# Fast_Servo.net
KiCad netlist of a schematic drawn in Altium Designer
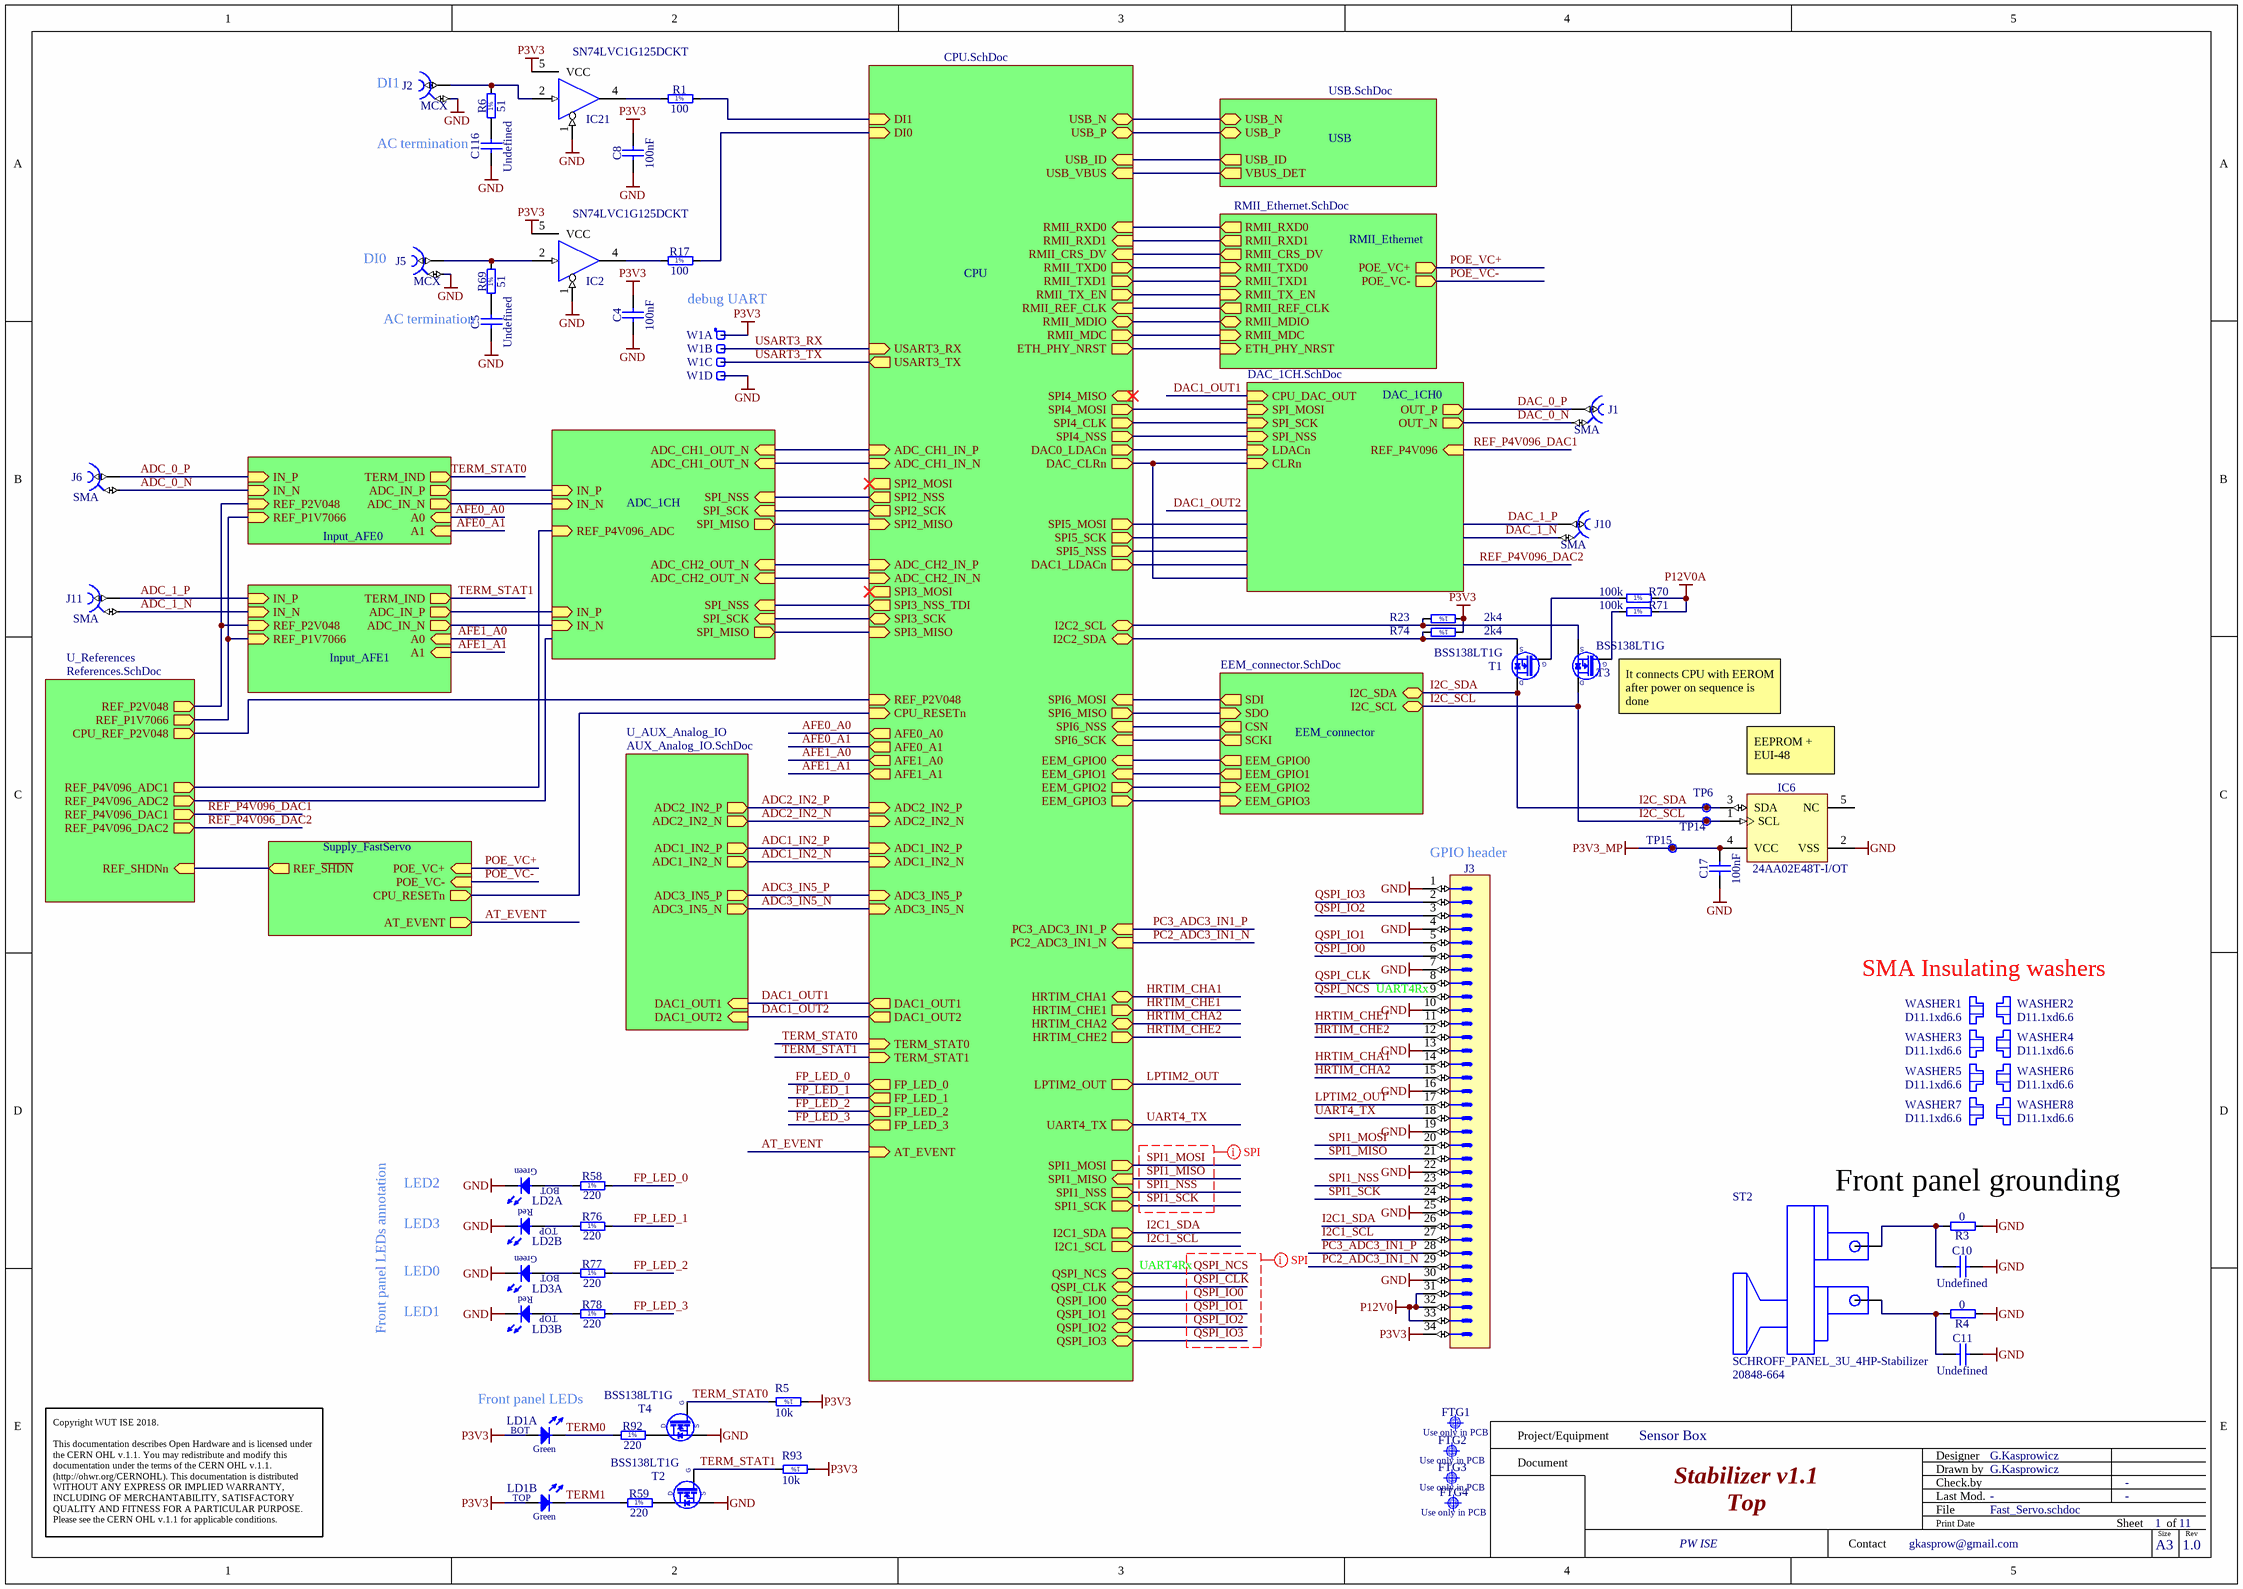
[diagram p0: Fast_Servo.schdoc]

(export (version "E")
  (design (tool "Eeschema 10.0.6"))
  (components
    (comp (ref "C4")
      (value "100nF")
      (footprint "CAPC1005X55N")
      (description "Non-polarised capacitor")
      (fields
        (field (name "PART NUMBER") "CC0402_100NF_16V_10%_X7R")
        (field (name "VOLTAGE") "16V")
        (field (name "AUTHOR") "CERN DEM JLC")
      )
      (libsource (lib "Capacitors") (part "Capacitor - non polarized"))
    )
    (comp (ref "C5")
      (value "Undefined")
      (footprint "CAPC1608X90N")
      (description "Non-polarised capacitor")
      (fields (field (name "PART NUMBER") "CC0603_NO-VALUE") (field (name "AUTHOR") "CERN DEM MR"))
      (libsource (lib "Capacitors") (part "Capacitor - non polarized"))
    )
    (comp (ref "C8")
      (value "100nF")
      (footprint "CAPC1005X55N")
      (description "Non-polarised capacitor")
      (fields
        (field (name "PART NUMBER") "CC0402_100NF_16V_10%_X7R")
        (field (name "VOLTAGE") "16V")
        (field (name "AUTHOR") "CERN DEM JLC")
      )
      (libsource (lib "Capacitors") (part "Capacitor - non polarized"))
    )
    (comp (ref "C10")
      (value "Undefined")
      (footprint "CAPC2012X135N")
      (description "Non-polarised capacitor")
      (fields (field (name "PART NUMBER") "CC0805_NO-VALUE") (field (name "AUTHOR") "CERN DEM JLC"))
      (libsource (lib "Capacitors") (part "Capacitor - non polarized"))
    )
    (comp (ref "C11")
      (value "Undefined")
      (footprint "CAPC2012X135N")
      (description "Non-polarised capacitor")
      (fields (field (name "PART NUMBER") "CC0805_NO-VALUE") (field (name "AUTHOR") "CERN DEM JLC"))
      (libsource (lib "Capacitors") (part "Capacitor - non polarized"))
    )
    (comp (ref "C17")
      (value "100nF")
      (footprint "CAPC1005X55N")
      (description "Non-polarised capacitor")
      (fields
        (field (name "PART NUMBER") "CC0402_100NF_16V_10%_X5R")
        (field (name "VOLTAGE") "16V")
        (field (name "AUTHOR") "CERN DEM JLC")
      )
      (libsource (lib "Capacitors") (part "Capacitor - non polarized"))
    )
    (comp (ref "C116")
      (value "Undefined")
      (footprint "CAPC1608X90N")
      (description "Non-polarised capacitor")
      (fields (field (name "PART NUMBER") "CC0603_NO-VALUE") (field (name "AUTHOR") "CERN DEM MR"))
      (libsource (lib "Capacitors") (part "Capacitor - non polarized"))
    )
    (comp (ref "FTG1")
      (value "Use only in PCB")
      (footprint "FIDUCIAL_TOP_C100-200")
      (description "Fiducial Target")
      (fields (field (name "PART NUMBER") "FIDUCIAL_TARGET_C100-200") (field (name "AUTHOR") "CERN DEM JLC"))
      (libsource (lib "Eletro-mechanical") (part "Fiducial Target"))
    )
    (comp (ref "FTG2")
      (value "Use only in PCB")
      (footprint "FIDUCIAL_TOP_S100-200")
      (description "Fiducial Target")
      (fields (field (name "PART NUMBER") "FIDUCIAL_TARGET_S100-200") (field (name "AUTHOR") "CERN DEM JLC"))
      (libsource (lib "Eletro-mechanical") (part "Fiducial Target"))
    )
    (comp (ref "FTG3")
      (value "Use only in PCB")
      (footprint "FIDUCIAL_TOP_S100-200")
      (description "Fiducial Target")
      (fields (field (name "PART NUMBER") "FIDUCIAL_TARGET_S100-200") (field (name "AUTHOR") "CERN DEM JLC"))
      (libsource (lib "Eletro-mechanical") (part "Fiducial Target"))
    )
    (comp (ref "FTG4")
      (value "Use only in PCB")
      (footprint "FIDUCIAL_TOP_S100-200")
      (description "Fiducial Target")
      (fields (field (name "PART NUMBER") "FIDUCIAL_TARGET_S100-200") (field (name "AUTHOR") "CERN DEM JLC"))
      (libsource (lib "Eletro-mechanical") (part "Fiducial Target"))
    )
    (comp (ref "IC2")
      (value "SN74LVC1G125DCKT")
      (footprint "SOT65P210X110-5N")
      (description "Single Bus Buffer Gate With 3-State Output")
      (fields (field (name "MANUFACTURER") "TEXAS INSTRUMENTS") (field (name "AUTHOR") "CERN DEM JLC"))
      (libsource (lib "ICs And Semiconductors") (part "741G125"))
    )
    (comp (ref "IC6")
      (value "24AA02E48T-I/OT")
      (footprint "SOT95P280X145-5N")
      (description "1.7V-5.5V, 2K I2C Serial EEPROM With EUI-48 Node Identity")
      (fields (field (name "MANUFACTURER") "MICROCHIP TECHNOLOGY") (field (name "AUTHOR") "CERN DEM MR"))
      (libsource (lib "ICs And Semiconductors") (part "24AA02E48T-I/OT"))
    )
    (comp (ref "IC21")
      (value "SN74LVC1G125DCKT")
      (footprint "SOT65P210X110-5N")
      (description "Single Bus Buffer Gate With 3-State Output")
      (fields (field (name "MANUFACTURER") "TEXAS INSTRUMENTS") (field (name "AUTHOR") "CERN DEM JLC"))
      (libsource (lib "ICs And Semiconductors") (part "741G125"))
    )
    (comp (ref "J1")
      (value "SMA")
      (footprint "RF249BT0050GHDW")
      (description "50 Ohm Through Hole SMA Right Angle PCB Jack")
      (fields
        (field (name "PART NUMBER") "AdamTech_RF249BT0050GHDW")
        (field (name "MANUFACTURER") "AdamTech")
        (field (name "AUTHOR") "GK")
      )
      (libsource (lib "LIBRARY_SCH") (part "CON_SMA_RF249BT0050GHDW"))
    )
    (comp (ref "J2")
      (value "MCX")
      (footprint "AMPHENOL_919-383J-51A")
      (fields
        (field (name "PART NUMBER") "AMPHENOL_919-383J-51A")
        (field (name "MANUFACTURER") "AMPHENOL")
        (field (name "MANUFACTURER PART NUMBER") "919-383J-51A")
        (field (name "AUTHOR") "CERN DEM BC")
      )
      (libsource (lib "Connectors") (part "Coax_1Female_1Shield"))
    )
    (comp (ref "J3")
      (value "Header 34")
      (footprint "3M_N2534-6002RB")
      (description "Connector 34 Male")
      (fields
        (field (name "PART NUMBER") "3M_N2534-6002RB")
        (field (name "MANUFACTURER") "3M")
        (field (name "AUTHOR") "CERN DEM JLC")
      )
      (libsource (lib "Connectors") (part "Connector 34 Male"))
    )
    (comp (ref "J5")
      (value "MCX")
      (footprint "AMPHENOL_919-383J-51A")
      (fields
        (field (name "PART NUMBER") "AMPHENOL_919-383J-51A")
        (field (name "MANUFACTURER") "AMPHENOL")
        (field (name "MANUFACTURER PART NUMBER") "919-383J-51A")
        (field (name "AUTHOR") "CERN DEM BC")
      )
      (libsource (lib "Connectors") (part "Coax_1Female_1Shield"))
    )
    (comp (ref "J6")
      (value "SMA")
      (footprint "RF249BT0050GHDW")
      (description "50 Ohm Through Hole SMA Right Angle PCB Jack")
      (fields
        (field (name "PART NUMBER") "AdamTech_RF249BT0050GHDW")
        (field (name "MANUFACTURER") "AdamTech")
        (field (name "AUTHOR") "GK")
      )
      (libsource (lib "") (part "CON_SMA_RF249BT0050GHDW_1"))
    )
    (comp (ref "J10")
      (value "SMA")
      (footprint "RF249BT0050GHDW")
      (description "50 Ohm Through Hole SMA Right Angle PCB Jack")
      (fields
        (field (name "PART NUMBER") "AdamTech_RF249BT0050GHDW")
        (field (name "MANUFACTURER") "AdamTech")
        (field (name "AUTHOR") "GK")
      )
      (libsource (lib "LIBRARY_SCH") (part "CON_SMA_RF249BT0050GHDW"))
    )
    (comp (ref "J11")
      (value "SMA")
      (footprint "RF249BT0050GHDW")
      (description "50 Ohm Through Hole SMA Right Angle PCB Jack")
      (fields
        (field (name "PART NUMBER") "AdamTech_RF249BT0050GHDW")
        (field (name "MANUFACTURER") "AdamTech")
        (field (name "AUTHOR") "GK")
      )
      (libsource (lib "") (part "CON_SMA_RF249BT0050GHDW_1"))
    )
    (comp (ref "LD1")
      (value "Green/Green")
      (footprint "LED_DIALIGHT_571-0122F")
      (description "LED x2 Green 1C2A-BOT_3C4A-TOP")
      (fields
        (field (name "PART NUMBER") "LED_DIALIGHT_571-0122F")
        (field (name "MANUFACTURER") "DIALIGHT")
        (field (name "AUTHOR") "CERN DEM JLC")
      )
      (libsource (lib "ICs And Semiconductors") (part "LED x2 Green 1C2A-BOT_3C4A-TOP"))
    )
    (comp (ref "LD2")
      (value "Red/Green")
      (footprint "LED_DIALIGHT_571-0112F")
      (description "2x LED  Botom Green, Top Red")
      (fields
        (field (name "PART NUMBER") "LED_DIALIGHT_571-0112F")
        (field (name "MANUFACTURER") "DIALIGHT")
        (field (name "AUTHOR") "CERN DEM JLC")
      )
      (libsource (lib "ICs And Semiconductors") (part "LED x2 G-1C2A-BOT_R-3C4A-TOP"))
    )
    (comp (ref "LD3")
      (value "Red/Green")
      (footprint "LED_DIALIGHT_571-0112F")
      (description "2x LED  Botom Green, Top Red")
      (fields
        (field (name "PART NUMBER") "LED_DIALIGHT_571-0112F")
        (field (name "MANUFACTURER") "DIALIGHT")
        (field (name "AUTHOR") "CERN DEM JLC")
      )
      (libsource (lib "ICs And Semiconductors") (part "LED x2 G-1C2A-BOT_R-3C4A-TOP"))
    )
    (comp (ref "R1")
      (value "100")
      (footprint "RESC1005X40N")
      (description "Resistor - 1%")
      (fields
        (field (name "PART NUMBER") "R0402_100R_1%_0.1W_100PPM")
        (field (name "POWER") "0.1W")
        (field (name "AUTHOR") "CERN DEM JLC")
      )
      (libsource (lib "Resistors") (part "Resistor - 1%"))
    )
    (comp (ref "R3")
      (value "0")
      (footprint "RESC1608X55N")
      (description "Resistor")
      (fields
        (field (name "PART NUMBER") "R0603_0R_JUMPER")
        (field (name "MANUFACTURER") "GENERIC")
        (field (name "AUTHOR") "CERN DEM JLC")
      )
      (libsource (lib "Resistors") (part "Resistor"))
    )
    (comp (ref "R4")
      (value "0")
      (footprint "RESC1608X55N")
      (description "Resistor")
      (fields
        (field (name "PART NUMBER") "R0603_0R_JUMPER")
        (field (name "MANUFACTURER") "GENERIC")
        (field (name "AUTHOR") "CERN DEM JLC")
      )
      (libsource (lib "Resistors") (part "Resistor"))
    )
    (comp (ref "R5")
      (value "10k")
      (footprint "RESC1005X40N")
      (description "Resistor - 1%")
      (fields
        (field (name "PART NUMBER") "R0402_10K_1%_0.0625W_100PPM")
        (field (name "POWER") "0.0625W")
        (field (name "AUTHOR") "CERN DEM JLC")
      )
      (libsource (lib "Resistors") (part "Resistor - 1%"))
    )
    (comp (ref "R6")
      (value "51")
      (footprint "RESC1005X40N")
      (description "Resistor - 1%")
      (fields
        (field (name "PART NUMBER") "R0402_51R_1%_0.0625W_100PPM")
        (field (name "POWER") "0.0625W")
        (field (name "AUTHOR") "CERN DEM JLC")
      )
      (libsource (lib "Resistors") (part "Resistor - 1%"))
    )
    (comp (ref "R17")
      (value "100")
      (footprint "RESC1005X40N")
      (description "Resistor - 1%")
      (fields
        (field (name "PART NUMBER") "R0402_100R_1%_0.1W_100PPM")
        (field (name "POWER") "0.1W")
        (field (name "AUTHOR") "CERN DEM JLC")
      )
      (libsource (lib "Resistors") (part "Resistor - 1%"))
    )
    (comp (ref "R23")
      (value "2k4")
      (footprint "RESC1005X40N")
      (description "Resistor - 1%")
      (fields
        (field (name "PART NUMBER") "R0402_2K4_1%_0.0625W_100PPM")
        (field (name "POWER") "0.0625W")
        (field (name "AUTHOR") "CERN DEM JLC")
      )
      (libsource (lib "Resistors") (part "Resistor - 1%"))
    )
    (comp (ref "R58")
      (value "220")
      (footprint "RESC1608X55N")
      (description "Resistor - 1%")
      (fields
        (field (name "PART NUMBER") "R0603_220R_1%_0.1W_100PPM")
        (field (name "POWER") "0.1W")
        (field (name "AUTHOR") "CERN DEM JLC")
      )
      (libsource (lib "Resistors") (part "Resistor - 1%"))
    )
    (comp (ref "R59")
      (value "220")
      (footprint "RESC1608X55N")
      (description "Resistor - 1%")
      (fields
        (field (name "PART NUMBER") "R0603_220R_1%_0.1W_100PPM")
        (field (name "POWER") "0.1W")
        (field (name "AUTHOR") "CERN DEM JLC")
      )
      (libsource (lib "Resistors") (part "Resistor - 1%"))
    )
    (comp (ref "R69")
      (value "51")
      (footprint "RESC1005X40N")
      (description "Resistor - 1%")
      (fields
        (field (name "PART NUMBER") "R0402_51R_1%_0.0625W_100PPM")
        (field (name "POWER") "0.0625W")
        (field (name "AUTHOR") "CERN DEM JLC")
      )
      (libsource (lib "Resistors") (part "Resistor - 1%"))
    )
    (comp (ref "R70")
      (value "100k")
      (footprint "RESC1005X40N")
      (description "Resistor - 1%")
      (fields
        (field (name "PART NUMBER") "R0402_100K_1%_0.0625W_100PPM")
        (field (name "POWER") "0.0625W")
        (field (name "AUTHOR") "CERN DEM JLC")
      )
      (libsource (lib "Resistors") (part "Resistor - 1%"))
    )
    (comp (ref "R71")
      (value "100k")
      (footprint "RESC1005X40N")
      (description "Resistor - 1%")
      (fields
        (field (name "PART NUMBER") "R0402_100K_1%_0.0625W_100PPM")
        (field (name "POWER") "0.0625W")
        (field (name "AUTHOR") "CERN DEM JLC")
      )
      (libsource (lib "Resistors") (part "Resistor - 1%"))
    )
    (comp (ref "R74")
      (value "2k4")
      (footprint "RESC1005X40N")
      (description "Resistor - 1%")
      (fields
        (field (name "PART NUMBER") "R0402_2K4_1%_0.0625W_100PPM")
        (field (name "POWER") "0.0625W")
        (field (name "AUTHOR") "CERN DEM JLC")
      )
      (libsource (lib "Resistors") (part "Resistor - 1%"))
    )
    (comp (ref "R76")
      (value "220")
      (footprint "RESC1608X55N")
      (description "Resistor - 1%")
      (fields
        (field (name "PART NUMBER") "R0603_220R_1%_0.1W_100PPM")
        (field (name "POWER") "0.1W")
        (field (name "AUTHOR") "CERN DEM JLC")
      )
      (libsource (lib "Resistors") (part "Resistor - 1%"))
    )
    (comp (ref "R77")
      (value "220")
      (footprint "RESC1608X55N")
      (description "Resistor - 1%")
      (fields
        (field (name "PART NUMBER") "R0603_220R_1%_0.1W_100PPM")
        (field (name "POWER") "0.1W")
        (field (name "AUTHOR") "CERN DEM JLC")
      )
      (libsource (lib "Resistors") (part "Resistor - 1%"))
    )
    (comp (ref "R78")
      (value "220")
      (footprint "RESC1608X55N")
      (description "Resistor - 1%")
      (fields
        (field (name "PART NUMBER") "R0603_220R_1%_0.1W_100PPM")
        (field (name "POWER") "0.1W")
        (field (name "AUTHOR") "CERN DEM JLC")
      )
      (libsource (lib "Resistors") (part "Resistor - 1%"))
    )
    (comp (ref "R92")
      (value "220")
      (footprint "RESC1608X55N")
      (description "Resistor - 1%")
      (fields
        (field (name "PART NUMBER") "R0603_220R_1%_0.1W_100PPM")
        (field (name "POWER") "0.1W")
        (field (name "AUTHOR") "CERN DEM JLC")
      )
      (libsource (lib "Resistors") (part "Resistor - 1%"))
    )
    (comp (ref "R93")
      (value "10k")
      (footprint "RESC1005X40N")
      (description "Resistor - 1%")
      (fields
        (field (name "PART NUMBER") "R0402_10K_1%_0.0625W_100PPM")
        (field (name "POWER") "0.0625W")
        (field (name "AUTHOR") "CERN DEM JLC")
      )
      (libsource (lib "Resistors") (part "Resistor - 1%"))
    )
    (comp (ref "ST2")
      (value "SCHROFF_PANEL_3U_4HP-Stabilizer")
      (footprint "SCHROFF_PANEL_3HP_4U - Stabilizer")
      (description "Schroff 3HP 4U EUROCARD Panel")
      (fields
        (field (name "MANUFACTURER") "Schroff")
        (field (name "MANUFACTURER PART NUMBER") "20818-017")
        (field (name "MANUFACTURER PART NUMBER 2") "20848-664")
      )
      (libsource (lib "Mechanical") (part "SCHROFF_PANEL_3U_4HP_Stabilizer"))
    )
    (comp (ref "T1")
      (value "BSS138LT1G")
      (footprint "SOT95P240X110-3N")
      (description "N-CHANNEL MOSFET WITH DIODE")
      (fields (field (name "MANUFACTURER") "ON SEMICONDUCTOR") (field (name "AUTHOR") "CERN DEM JLC"))
      (libsource (lib "ICs And Semiconductors") (part "N-MOSFET-D 1G 2S 3D"))
    )
    (comp (ref "T2")
      (value "BSS138LT1G")
      (footprint "SOT95P240X110-3N")
      (description "N-CHANNEL MOSFET WITH DIODE")
      (fields (field (name "MANUFACTURER") "ON SEMICONDUCTOR") (field (name "AUTHOR") "CERN DEM JLC"))
      (libsource (lib "ICs And Semiconductors") (part "N-MOSFET-D 1G 2S 3D"))
    )
    (comp (ref "T3")
      (value "BSS138LT1G")
      (footprint "SOT95P240X110-3N")
      (description "N-CHANNEL MOSFET WITH DIODE")
      (fields (field (name "MANUFACTURER") "ON SEMICONDUCTOR") (field (name "AUTHOR") "CERN DEM JLC"))
      (libsource (lib "ICs And Semiconductors") (part "N-MOSFET-D 1G 2S 3D"))
    )
    (comp (ref "T4")
      (value "BSS138LT1G")
      (footprint "SOT95P240X110-3N")
      (description "N-CHANNEL MOSFET WITH DIODE")
      (fields (field (name "MANUFACTURER") "ON SEMICONDUCTOR") (field (name "AUTHOR") "CERN DEM JLC"))
      (libsource (lib "ICs And Semiconductors") (part "N-MOSFET-D 1G 2S 3D"))
    )
    (comp (ref "TP6")
      (value "Test Point")
      (footprint "TPS127")
      (fields (field (name "PART NUMBER") "SMD_PAD_1.27X1.27MM") (field (name "AUTHOR") "CERN DEM JLC"))
      (libsource (lib "Eletro-mechanical") (part "Test Point"))
    )
    (comp (ref "TP14")
      (value "Test Point")
      (footprint "TPS127")
      (fields (field (name "PART NUMBER") "SMD_PAD_1.27X1.27MM") (field (name "AUTHOR") "CERN DEM JLC"))
      (libsource (lib "Eletro-mechanical") (part "Test Point"))
    )
    (comp (ref "TP15")
      (value "Test Point")
      (footprint "TPS127")
      (fields (field (name "PART NUMBER") "SMD_PAD_1.27X1.27MM") (field (name "AUTHOR") "CERN DEM JLC"))
      (libsource (lib "Eletro-mechanical") (part "Test Point"))
    )
    (comp (ref "W1")
      (value "Header 4")
      (footprint "SAMTEC_HTSW-104-23-L-S")
      (description "4 Mini Wire-Wrap Contact Strip Header")
      (fields
        (field (name "PART NUMBER") "SAMTEC_HTSW-104-23-L-S")
        (field (name "MANUFACTURER") "SAMTEC")
        (field (name "AUTHOR") "CERN DEM JLC")
      )
      (libsource (lib "Connectors") (part "Wire-Wrap Contact x4"))
    )
    (comp (ref "WASHER1")
      (value "D11.1xd6.6")
      (footprint "Keystone_7687")
      (description "SMA_Shoulder Washer")
      (fields
        (field (name "PART NUMBER") "Keystone 7687")
        (field (name "MANUFACTURER") "Keystone")
        (field (name "AUTHOR") "GK")
      )
      (libsource (lib "LIBRARY_SCH") (part "Keystone_7687"))
    )
    (comp (ref "WASHER2")
      (value "D11.1xd6.6")
      (footprint "Keystone_7687")
      (description "SMA_Shoulder Washer")
      (fields
        (field (name "PART NUMBER") "Keystone 7687")
        (field (name "MANUFACTURER") "Keystone")
        (field (name "AUTHOR") "GK")
      )
      (libsource (lib "LIBRARY_SCH") (part "Keystone_7687"))
    )
    (comp (ref "WASHER3")
      (value "D11.1xd6.6")
      (footprint "Keystone_7687")
      (description "SMA_Shoulder Washer")
      (fields
        (field (name "PART NUMBER") "Keystone 7687")
        (field (name "MANUFACTURER") "Keystone")
        (field (name "AUTHOR") "GK")
      )
      (libsource (lib "LIBRARY_SCH") (part "Keystone_7687"))
    )
    (comp (ref "WASHER4")
      (value "D11.1xd6.6")
      (footprint "Keystone_7687")
      (description "SMA_Shoulder Washer")
      (fields
        (field (name "PART NUMBER") "Keystone 7687")
        (field (name "MANUFACTURER") "Keystone")
        (field (name "AUTHOR") "GK")
      )
      (libsource (lib "LIBRARY_SCH") (part "Keystone_7687"))
    )
    (comp (ref "WASHER5")
      (value "D11.1xd6.6")
      (footprint "Keystone_7687")
      (description "SMA_Shoulder Washer")
      (fields
        (field (name "PART NUMBER") "Keystone 7687")
        (field (name "MANUFACTURER") "Keystone")
        (field (name "AUTHOR") "GK")
      )
      (libsource (lib "LIBRARY_SCH") (part "Keystone_7687"))
    )
    (comp (ref "WASHER6")
      (value "D11.1xd6.6")
      (footprint "Keystone_7687")
      (description "SMA_Shoulder Washer")
      (fields
        (field (name "PART NUMBER") "Keystone 7687")
        (field (name "MANUFACTURER") "Keystone")
        (field (name "AUTHOR") "GK")
      )
      (libsource (lib "LIBRARY_SCH") (part "Keystone_7687"))
    )
    (comp (ref "WASHER7")
      (value "D11.1xd6.6")
      (footprint "Keystone_7687")
      (description "SMA_Shoulder Washer")
      (fields
        (field (name "PART NUMBER") "Keystone 7687")
        (field (name "MANUFACTURER") "Keystone")
        (field (name "AUTHOR") "GK")
      )
      (libsource (lib "LIBRARY_SCH") (part "Keystone_7687"))
    )
    (comp (ref "WASHER8")
      (value "D11.1xd6.6")
      (footprint "Keystone_7687")
      (description "SMA_Shoulder Washer")
      (fields
        (field (name "PART NUMBER") "Keystone 7687")
        (field (name "MANUFACTURER") "Keystone")
        (field (name "AUTHOR") "GK")
      )
      (libsource (lib "LIBRARY_SCH") (part "Keystone_7687"))
    )
  )
  (nets
    (net (code "7") (name "/ADC_0_N") (class "Default")
      (node (ref "J6") (pin "2") (pinfunction "2_2") (pintype "bidirectional"))
    )
    (net (code "8") (name "/ADC_0_P") (class "Default")
      (node (ref "J6") (pin "1") (pinfunction "1_1") (pintype "bidirectional"))
    )
    (net (code "9") (name "/ADC_1_N") (class "Default")
      (node (ref "J11") (pin "2") (pinfunction "2_2") (pintype "bidirectional"))
    )
    (net (code "10") (name "/ADC_1_P") (class "Default")
      (node (ref "J11") (pin "1") (pinfunction "1_1") (pintype "bidirectional"))
    )
    (net (code "31") (name "/DAC_0_N") (class "Default")
      (node (ref "J1") (pin "2") (pinfunction "2_2") (pintype "bidirectional"))
    )
    (net (code "32") (name "/DAC_0_P") (class "Default")
      (node (ref "J1") (pin "1") (pinfunction "1_1") (pintype "bidirectional"))
    )
    (net (code "33") (name "/DAC_1_N") (class "Default")
      (node (ref "J10") (pin "2") (pinfunction "2_2") (pintype "bidirectional"))
    )
    (net (code "34") (name "/DAC_1_P") (class "Default")
      (node (ref "J10") (pin "1") (pinfunction "1_1") (pintype "bidirectional"))
    )
    (net (code "36") (name "/DI0") (class "Default")
      (node (ref "R17") (pin "2") (pinfunction "2_2") (pintype "passive"))
    )
    (net (code "37") (name "/DI1") (class "Default")
      (node (ref "R1") (pin "2") (pinfunction "2_2") (pintype "passive"))
    )
    (net (code "43") (name "/FP_LED_0") (class "Default")
      (node (ref "R58") (pin "2") (pinfunction "2_2") (pintype "passive"))
    )
    (net (code "44") (name "/FP_LED_1") (class "Default")
      (node (ref "R76") (pin "2") (pinfunction "2_2") (pintype "passive"))
    )
    (net (code "45") (name "/FP_LED_2") (class "Default")
      (node (ref "R77") (pin "2") (pinfunction "2_2") (pintype "passive"))
    )
    (net (code "46") (name "/FP_LED_3") (class "Default")
      (node (ref "R78") (pin "2") (pinfunction "2_2") (pintype "passive"))
    )
    (net (code "47") (name "/HRTIM_CHA1") (class "Default")
      (node (ref "J3") (pin "14") (pinfunction "14_14") (pintype "bidirectional"))
    )
    (net (code "48") (name "/HRTIM_CHA2") (class "Default")
      (node (ref "J3") (pin "15") (pinfunction "15_15") (pintype "bidirectional"))
    )
    (net (code "49") (name "/HRTIM_CHE1") (class "Default")
      (node (ref "J3") (pin "11") (pinfunction "11_11") (pintype "bidirectional"))
    )
    (net (code "50") (name "/HRTIM_CHE2") (class "Default")
      (node (ref "J3") (pin "12") (pinfunction "12_12") (pintype "bidirectional"))
    )
    (net (code "51") (name "/I2C1_SCL") (class "Default")
      (node (ref "J3") (pin "27") (pinfunction "27_27") (pintype "bidirectional"))
    )
    (net (code "52") (name "/I2C1_SDA") (class "Default")
      (node (ref "J3") (pin "26") (pinfunction "26_26") (pintype "bidirectional"))
    )
    (net (code "53") (name "/I2C2_SCL") (class "Default")
      (node (ref "R23") (pin "2") (pinfunction "2_2") (pintype "passive"))
      (node (ref "T3") (pin "2") (pinfunction "S_2") (pintype "passive"))
    )
    (net (code "54") (name "/I2C2_SDA") (class "Default")
      (node (ref "R74") (pin "2") (pinfunction "2_2") (pintype "passive"))
      (node (ref "T1") (pin "2") (pinfunction "S_2") (pintype "passive"))
    )
    (net (code "55") (name "/I2C_SCL") (class "Default")
      (node (ref "IC6") (pin "1") (pinfunction "SCL_1") (pintype "input"))
      (node (ref "T3") (pin "3") (pinfunction "D_3") (pintype "passive"))
      (node (ref "TP14") (pin "1") (pinfunction "1_1") (pintype "bidirectional"))
    )
    (net (code "56") (name "/I2C_SDA") (class "Default")
      (node (ref "IC6") (pin "3") (pinfunction "SDA_3") (pintype "bidirectional"))
      (node (ref "T1") (pin "3") (pinfunction "D_3") (pintype "passive"))
      (node (ref "TP6") (pin "1") (pinfunction "1_1") (pintype "bidirectional"))
    )
    (net (code "57") (name "/LPTIM2_OUT") (class "Default")
      (node (ref "J3") (pin "17") (pinfunction "17_17") (pintype "bidirectional"))
    )
    (net (code "58") (name "/PC2_ADC3_IN1_N") (class "Default")
      (node (ref "J3") (pin "29") (pinfunction "29_29") (pintype "bidirectional"))
    )
    (net (code "59") (name "/PC3_ADC3_IN1_P") (class "Default")
      (node (ref "J3") (pin "28") (pinfunction "28_28") (pintype "bidirectional"))
    )
    (net (code "62") (name "/QSPI_CLK") (class "Default")
      (node (ref "J3") (pin "8") (pinfunction "8_8") (pintype "bidirectional"))
    )
    (net (code "63") (name "/QSPI_IO0") (class "Default")
      (node (ref "J3") (pin "6") (pinfunction "6_6") (pintype "bidirectional"))
    )
    (net (code "64") (name "/QSPI_IO1") (class "Default")
      (node (ref "J3") (pin "5") (pinfunction "5_5") (pintype "bidirectional"))
    )
    (net (code "65") (name "/QSPI_IO2") (class "Default")
      (node (ref "J3") (pin "3") (pinfunction "3_3") (pintype "bidirectional"))
    )
    (net (code "66") (name "/QSPI_IO3") (class "Default")
      (node (ref "J3") (pin "2") (pinfunction "2_2") (pintype "bidirectional"))
    )
    (net (code "67") (name "/QSPI_NCS") (class "Default")
      (node (ref "J3") (pin "9") (pinfunction "9_9") (pintype "bidirectional"))
    )
    (net (code "86") (name "/SPI1_MISO") (class "Default")
      (node (ref "J3") (pin "21") (pinfunction "21_21") (pintype "bidirectional"))
    )
    (net (code "87") (name "/SPI1_MOSI") (class "Default")
      (node (ref "J3") (pin "20") (pinfunction "20_20") (pintype "bidirectional"))
    )
    (net (code "88") (name "/SPI1_NSS") (class "Default")
      (node (ref "J3") (pin "23") (pinfunction "23_23") (pintype "bidirectional"))
    )
    (net (code "89") (name "/SPI1_SCK") (class "Default")
      (node (ref "J3") (pin "24") (pinfunction "24_24") (pintype "bidirectional"))
    )
    (net (code "106") (name "/TERM0") (class "Default")
      (node (ref "LD1") (pin "1") (pinfunction "C_1") (pintype "passive"))
      (node (ref "R92") (pin "1") (pinfunction "1_1") (pintype "passive"))
    )
    (net (code "107") (name "/TERM1") (class "Default")
      (node (ref "LD1") (pin "3") (pinfunction "C_3") (pintype "passive"))
      (node (ref "R59") (pin "1") (pinfunction "1_1") (pintype "passive"))
    )
    (net (code "108") (name "/TERM_STAT0") (class "Default")
      (node (ref "R5") (pin "2") (pinfunction "2_2") (pintype "passive"))
      (node (ref "T4") (pin "1") (pinfunction "G_1") (pintype "passive"))
    )
    (net (code "109") (name "/TERM_STAT1") (class "Default")
      (node (ref "R93") (pin "2") (pinfunction "2_2") (pintype "passive"))
      (node (ref "T2") (pin "1") (pinfunction "G_1") (pintype "passive"))
    )
    (net (code "110") (name "/UART4_TX") (class "Default")
      (node (ref "J3") (pin "18") (pinfunction "18_18") (pintype "bidirectional"))
    )
    (net (code "111") (name "/USART3_RX") (class "Default")
      (node (ref "W1") (pin "2") (pinfunction "2_2") (pintype "bidirectional"))
    )
    (net (code "112") (name "/USART3_TX") (class "Default")
      (node (ref "W1") (pin "3") (pinfunction "3_3") (pintype "bidirectional"))
    )
    (net (code "117") (name "GND") (class "Default")
      (node (ref "C10") (pin "2") (pinfunction "2_2") (pintype "passive"))
      (node (ref "C11") (pin "2") (pinfunction "2_2") (pintype "passive"))
      (node (ref "C116") (pin "1") (pinfunction "1_1") (pintype "passive"))
      (node (ref "C17") (pin "1") (pinfunction "1_1") (pintype "passive"))
      (node (ref "C4") (pin "1") (pinfunction "1_1") (pintype "passive"))
      (node (ref "C5") (pin "1") (pinfunction "1_1") (pintype "passive"))
      (node (ref "C8") (pin "1") (pinfunction "1_1") (pintype "passive"))
      (node (ref "IC2") (pin "1") (pinfunction "~{G}_1") (pintype "input"))
      (node (ref "IC2") (pin "3") (pinfunction "GND_3") (pintype "power_in"))
      (node (ref "IC21") (pin "1") (pinfunction "~{G}_1") (pintype "input"))
      (node (ref "IC21") (pin "3") (pinfunction "GND_3") (pintype "power_in"))
      (node (ref "IC6") (pin "2") (pinfunction "VSS_2") (pintype "power_in"))
      (node (ref "J2") (pin "2") (pinfunction "2_2") (pintype "bidirectional"))
      (node (ref "J3") (pin "1") (pinfunction "1_1") (pintype "bidirectional"))
      (node (ref "J3") (pin "10") (pinfunction "10_10") (pintype "bidirectional"))
      (node (ref "J3") (pin "13") (pinfunction "13_13") (pintype "bidirectional"))
      (node (ref "J3") (pin "16") (pinfunction "16_16") (pintype "bidirectional"))
      (node (ref "J3") (pin "19") (pinfunction "19_19") (pintype "bidirectional"))
      (node (ref "J3") (pin "22") (pinfunction "22_22") (pintype "bidirectional"))
      (node (ref "J3") (pin "25") (pinfunction "25_25") (pintype "bidirectional"))
      (node (ref "J3") (pin "30") (pinfunction "30_30") (pintype "bidirectional"))
      (node (ref "J3") (pin "4") (pinfunction "4_4") (pintype "bidirectional"))
      (node (ref "J3") (pin "7") (pinfunction "7_7") (pintype "bidirectional"))
      (node (ref "J5") (pin "2") (pinfunction "2_2") (pintype "bidirectional"))
      (node (ref "LD2") (pin "1") (pinfunction "C_1") (pintype "passive"))
      (node (ref "LD2") (pin "3") (pinfunction "C_3") (pintype "passive"))
      (node (ref "LD3") (pin "1") (pinfunction "C_1") (pintype "passive"))
      (node (ref "LD3") (pin "3") (pinfunction "C_3") (pintype "passive"))
      (node (ref "R3") (pin "1") (pinfunction "1_1") (pintype "passive"))
      (node (ref "R4") (pin "1") (pinfunction "1_1") (pintype "passive"))
      (node (ref "T2") (pin "2") (pinfunction "S_2") (pintype "passive"))
      (node (ref "T4") (pin "2") (pinfunction "S_2") (pintype "passive"))
      (node (ref "W1") (pin "4") (pinfunction "4_4") (pintype "bidirectional"))
    )
    (net (code "118") (name "Net-(C5-Pad2)") (class "Default")
      (node (ref "C5") (pin "2") (pinfunction "2_2") (pintype "passive"))
      (node (ref "R69") (pin "1") (pinfunction "1_1") (pintype "passive"))
    )
    (net (code "119") (name "Net-(C10-Pad1)") (class "Default")
      (node (ref "C10") (pin "1") (pinfunction "1_1") (pintype "passive"))
      (node (ref "R3") (pin "2") (pinfunction "2_2") (pintype "passive"))
      (node (ref "ST2") (pin "1") (pinfunction "1_1") (pintype "passive"))
    )
    (net (code "120") (name "Net-(C11-Pad1)") (class "Default")
      (node (ref "C11") (pin "1") (pinfunction "1_1") (pintype "passive"))
      (node (ref "R4") (pin "2") (pinfunction "2_2") (pintype "passive"))
      (node (ref "ST2") (pin "0") (pinfunction "0_0") (pintype "passive"))
    )
    (net (code "121") (name "Net-(C116-Pad2)") (class "Default")
      (node (ref "C116") (pin "2") (pinfunction "2_2") (pintype "passive"))
      (node (ref "R6") (pin "1") (pinfunction "1_1") (pintype "passive"))
    )
    (net (code "122") (name "Net-(IC2-IN)") (class "Default")
      (node (ref "IC2") (pin "2") (pinfunction "IN_2") (pintype "input"))
      (node (ref "J5") (pin "1") (pinfunction "1_1") (pintype "bidirectional"))
      (node (ref "R69") (pin "2") (pinfunction "2_2") (pintype "passive"))
    )
    (net (code "123") (name "Net-(IC2-OUT)") (class "Default")
      (node (ref "IC2") (pin "4") (pinfunction "OUT_4") (pintype "tri_state"))
      (node (ref "R17") (pin "1") (pinfunction "1_1") (pintype "passive"))
    )
    (net (code "124") (name "Net-(IC21-IN)") (class "Default")
      (node (ref "IC21") (pin "2") (pinfunction "IN_2") (pintype "input"))
      (node (ref "J2") (pin "1") (pinfunction "1_1") (pintype "bidirectional"))
      (node (ref "R6") (pin "2") (pinfunction "2_2") (pintype "passive"))
    )
    (net (code "125") (name "Net-(IC21-OUT)") (class "Default")
      (node (ref "IC21") (pin "4") (pinfunction "OUT_4") (pintype "tri_state"))
      (node (ref "R1") (pin "1") (pinfunction "1_1") (pintype "passive"))
    )
    (net (code "126") (name "Net-(LD2A-A)") (class "Default")
      (node (ref "LD2") (pin "2") (pinfunction "A_2") (pintype "passive"))
      (node (ref "R58") (pin "1") (pinfunction "1_1") (pintype "passive"))
    )
    (net (code "127") (name "Net-(LD2B-A)") (class "Default")
      (node (ref "LD2") (pin "4") (pinfunction "A_4") (pintype "passive"))
      (node (ref "R76") (pin "1") (pinfunction "1_1") (pintype "passive"))
    )
    (net (code "128") (name "Net-(LD3A-A)") (class "Default")
      (node (ref "LD3") (pin "2") (pinfunction "A_2") (pintype "passive"))
      (node (ref "R77") (pin "1") (pinfunction "1_1") (pintype "passive"))
    )
    (net (code "129") (name "Net-(LD3B-A)") (class "Default")
      (node (ref "LD3") (pin "4") (pinfunction "A_4") (pintype "passive"))
      (node (ref "R78") (pin "1") (pinfunction "1_1") (pintype "passive"))
    )
    (net (code "130") (name "Net-(T1-G)") (class "Default")
      (node (ref "R70") (pin "1") (pinfunction "1_1") (pintype "passive"))
      (node (ref "T1") (pin "1") (pinfunction "G_1") (pintype "passive"))
    )
    (net (code "131") (name "Net-(T2-D)") (class "Default")
      (node (ref "R59") (pin "2") (pinfunction "2_2") (pintype "passive"))
      (node (ref "T2") (pin "3") (pinfunction "D_3") (pintype "passive"))
    )
    (net (code "132") (name "Net-(T3-G)") (class "Default")
      (node (ref "R71") (pin "1") (pinfunction "1_1") (pintype "passive"))
      (node (ref "T3") (pin "1") (pinfunction "G_1") (pintype "passive"))
    )
    (net (code "133") (name "Net-(T4-D)") (class "Default")
      (node (ref "R92") (pin "2") (pinfunction "2_2") (pintype "passive"))
      (node (ref "T4") (pin "3") (pinfunction "D_3") (pintype "passive"))
    )
    (net (code "134") (name "P3V3") (class "Default")
      (node (ref "C4") (pin "2") (pinfunction "2_2") (pintype "passive"))
      (node (ref "C8") (pin "2") (pinfunction "2_2") (pintype "passive"))
      (node (ref "IC2") (pin "5") (pinfunction "VCC_5") (pintype "power_in"))
      (node (ref "IC21") (pin "5") (pinfunction "VCC_5") (pintype "power_in"))
      (node (ref "J3") (pin "34") (pinfunction "34_34") (pintype "bidirectional"))
      (node (ref "LD1") (pin "2") (pinfunction "A_2") (pintype "passive"))
      (node (ref "LD1") (pin "4") (pinfunction "A_4") (pintype "passive"))
      (node (ref "R23") (pin "1") (pinfunction "1_1") (pintype "passive"))
      (node (ref "R5") (pin "1") (pinfunction "1_1") (pintype "passive"))
      (node (ref "R74") (pin "1") (pinfunction "1_1") (pintype "passive"))
      (node (ref "R93") (pin "1") (pinfunction "1_1") (pintype "passive"))
      (node (ref "W1") (pin "1") (pinfunction "1_1") (pintype "bidirectional"))
    )
    (net (code "135") (name "P3V3_MP") (class "Default")
      (node (ref "C17") (pin "2") (pinfunction "2_2") (pintype "passive"))
      (node (ref "IC6") (pin "4") (pinfunction "VCC_4") (pintype "power_in"))
      (node (ref "TP15") (pin "1") (pinfunction "1_1") (pintype "bidirectional"))
    )
    (net (code "136") (name "P12V0") (class "Default")
      (node (ref "J3") (pin "31") (pinfunction "31_31") (pintype "bidirectional"))
      (node (ref "J3") (pin "32") (pinfunction "32_32") (pintype "bidirectional"))
      (node (ref "J3") (pin "33") (pinfunction "33_33") (pintype "bidirectional"))
    )
    (net (code "137") (name "P12V0A") (class "Default")
      (node (ref "R70") (pin "2") (pinfunction "2_2") (pintype "passive"))
      (node (ref "R71") (pin "2") (pinfunction "2_2") (pintype "passive"))
    )
    (net (code "138") (name "unconnected-(IC6-NC-Pad5)") (class "Default")
      (node (ref "IC6") (pin "5") (pinfunction "NC_5") (pintype "passive"))
    )
  )
)
